# BPU_display.net
KiCad netlist of a schematic drawn in EAGLE
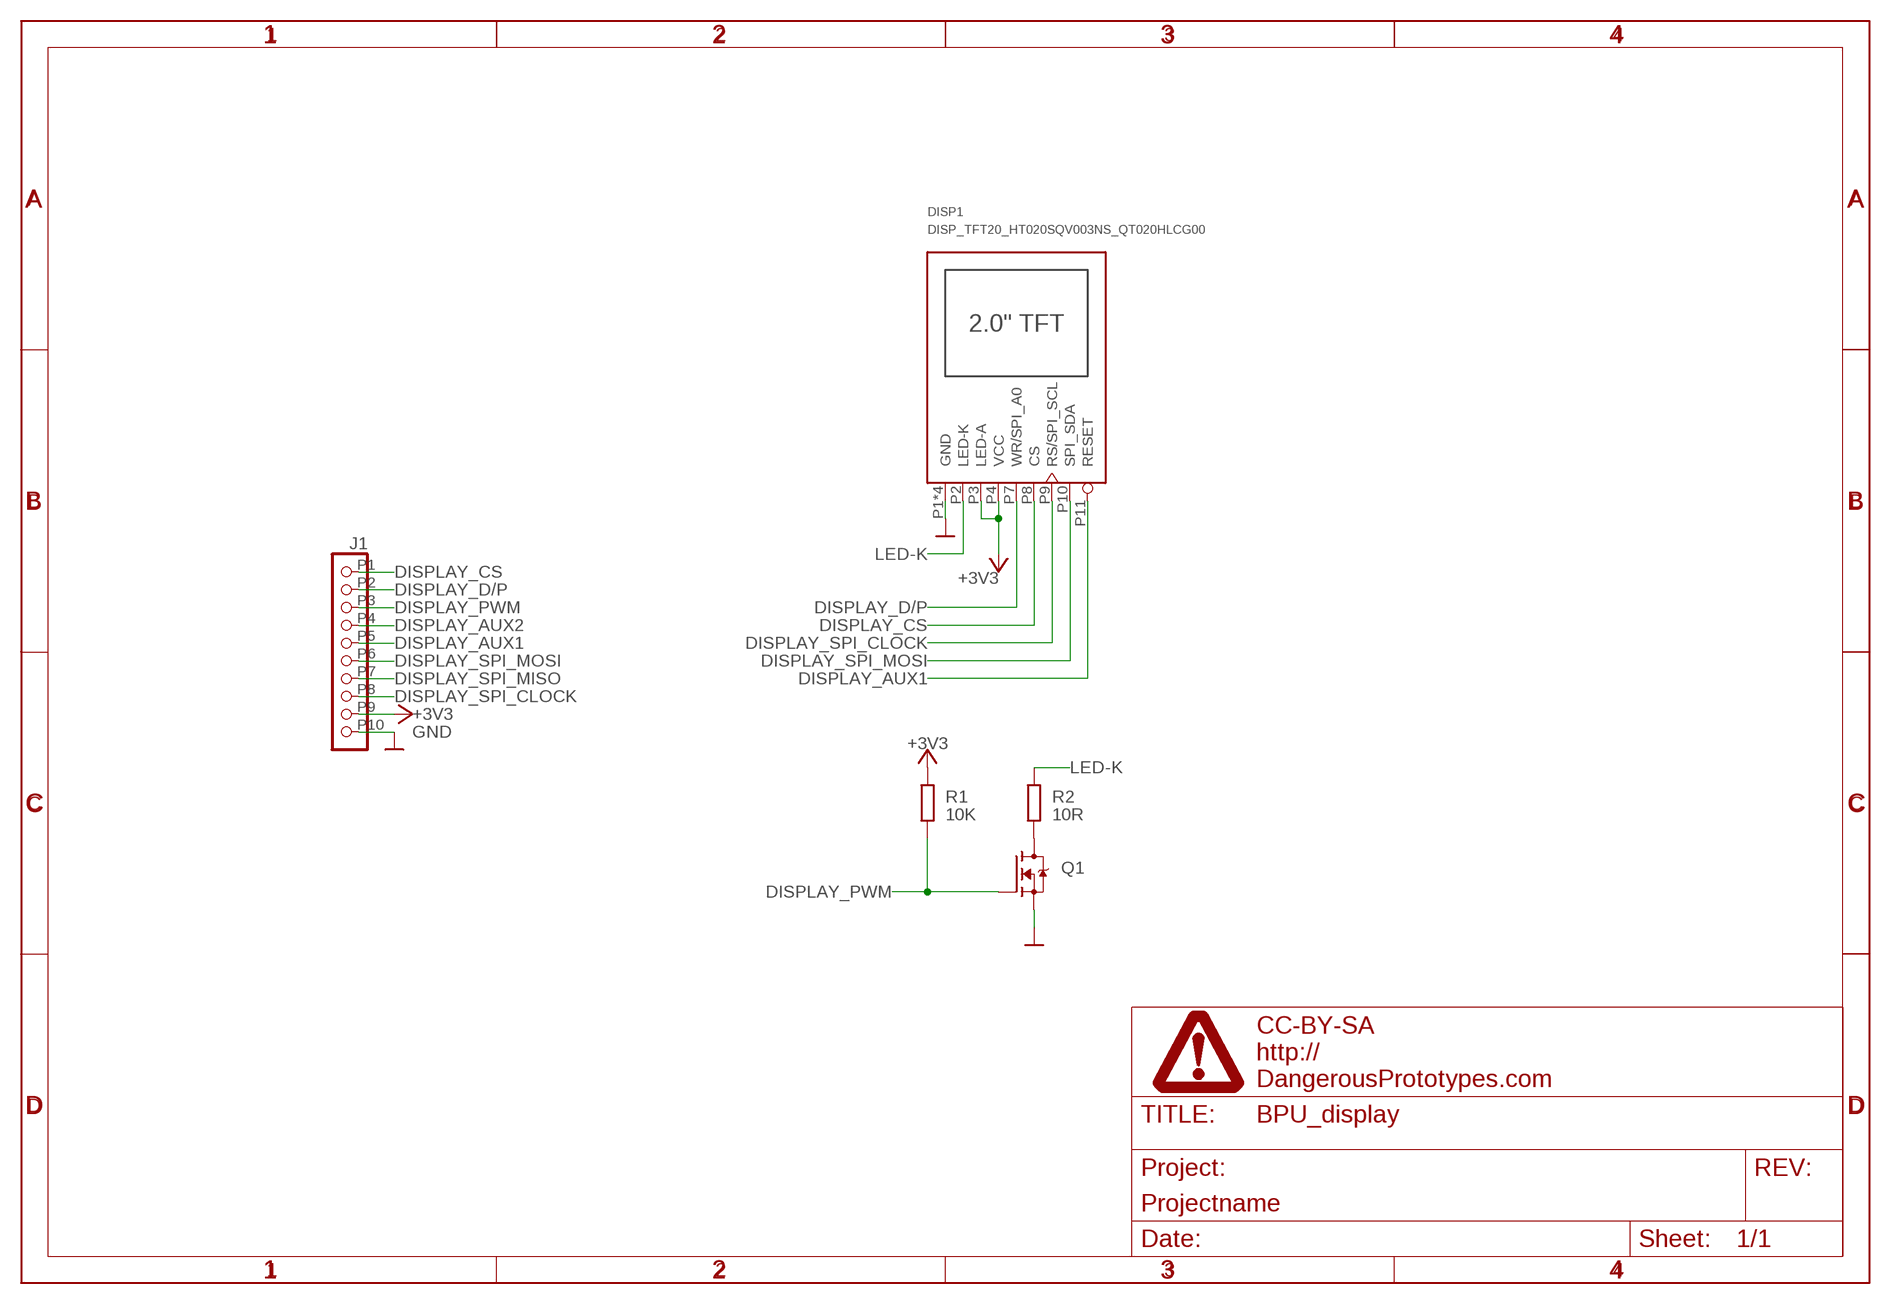
[diagram p0: schematic, sheet 1]

(export (version "E")
  (design (tool "Eeschema 10.0.6"))
  (components
    (comp (ref "DISP1")
      (value "DISP_TFT20_HT020SQV003NS_QT020HLCG00")
      (footprint "eagle-import:HT020SQV003NS_QT020HLCG00")
      (libsource (lib "eagle-import") (part "DISP_TFT20_HT020SQV003NS_QT020HLCG00"))
    )
    (comp (ref "J1")
      (value "CON_MOLEX_MALE_SMT_RIGHT_ANGLE_1.25")
      (footprint "eagle-import:MOLEX_532611071")
      (libsource (lib "eagle-import") (part "CON_MOLEX_MALE_SMT_RIGHT_ANGLE_1.25"))
    )
    (comp (ref "PAGE1")
      (value "FRAME_DINA4_L")
      (footprint "eagle-import:DP_LOGO")
      (libsource (lib "eagle-import") (part "FRAME_DINA4_L"))
    )
    (comp (ref "Q1")
      (value "TRANSISTOR_FET_BS170-SOT-23")
      (footprint "eagle-import:SOT-23")
      (libsource (lib "eagle-import") (part "TRANSISTOR_FET_BS170-SOT-23"))
    )
    (comp (ref "R1")
      (value "10K")
      (footprint "eagle-import:R0603")
      (libsource (lib "eagle-import") (part "R-EU_R0603"))
    )
    (comp (ref "R2")
      (value "10R")
      (footprint "eagle-import:R0603")
      (libsource (lib "eagle-import") (part "R-EU_R0603"))
    )
  )
  (nets
    (net (code "1") (name "/DISPLAY_AUX1") (class "Default")
      (node (ref "DISP1") (pin "P11") (pinfunction "RESET_P11") (pintype "input"))
      (node (ref "J1") (pin "P5") (pinfunction "5_P5") (pintype "passive"))
    )
    (net (code "2") (name "/DISPLAY_AUX2") (class "Default")
      (node (ref "J1") (pin "P4") (pinfunction "4_P4") (pintype "passive"))
    )
    (net (code "3") (name "/DISPLAY_CS") (class "Default")
      (node (ref "DISP1") (pin "P8") (pinfunction "CS_P8") (pintype "input"))
      (node (ref "J1") (pin "P1") (pinfunction "1_P1") (pintype "passive"))
    )
    (net (code "4") (name "/DISPLAY_D{slash}P") (class "Default")
      (node (ref "DISP1") (pin "P7") (pinfunction "WR/SPI_A0_P7") (pintype "input"))
      (node (ref "J1") (pin "P2") (pinfunction "2_P2") (pintype "passive"))
    )
    (net (code "5") (name "/DISPLAY_PWM") (class "Default")
      (node (ref "J1") (pin "P3") (pinfunction "3_P3") (pintype "passive"))
      (node (ref "Q1") (pin "1") (pinfunction "G_1") (pintype "passive"))
      (node (ref "R1") (pin "1") (pinfunction "1_1") (pintype "passive"))
    )
    (net (code "6") (name "/DISPLAY_SPI_CLOCK") (class "Default")
      (node (ref "DISP1") (pin "P9") (pinfunction "RS/SPI_SCL_P9") (pintype "input"))
      (node (ref "J1") (pin "P8") (pinfunction "8_P8") (pintype "passive"))
    )
    (net (code "7") (name "/DISPLAY_SPI_MISO") (class "Default")
      (node (ref "J1") (pin "P7") (pinfunction "7_P7") (pintype "passive"))
    )
    (net (code "8") (name "/DISPLAY_SPI_MOSI") (class "Default")
      (node (ref "DISP1") (pin "P10") (pinfunction "SPI_SDA_P10") (pintype "bidirectional"))
      (node (ref "J1") (pin "P6") (pinfunction "6_P6") (pintype "passive"))
    )
    (net (code "9") (name "/LED-K") (class "Default")
      (node (ref "DISP1") (pin "P2") (pinfunction "LED-K_P2") (pintype "power_in"))
      (node (ref "R2") (pin "2") (pinfunction "2_2") (pintype "passive"))
    )
    (net (code "10") (name "Net-(Q1-D)") (class "Default")
      (node (ref "Q1") (pin "3") (pinfunction "D_3") (pintype "passive"))
      (node (ref "R2") (pin "1") (pinfunction "1_1") (pintype "passive"))
    )
    (net (code "11") (name "SUPPLY_+3V3") (class "Default")
      (node (ref "DISP1") (pin "P3") (pinfunction "LED-A_P3") (pintype "power_in"))
      (node (ref "DISP1") (pin "P4") (pinfunction "VCC_P4") (pintype "power_in"))
      (node (ref "J1") (pin "P9") (pinfunction "9_P9") (pintype "passive"))
      (node (ref "R1") (pin "2") (pinfunction "2_2") (pintype "passive"))
    )
    (net (code "12") (name "SUPPLY_GND") (class "Default")
      (node (ref "DISP1") (pin "P1") (pinfunction "GND_P1") (pintype "power_in"))
      (node (ref "DISP1") (pin "P12") (pinfunction "GND_P12") (pintype "power_in"))
      (node (ref "DISP1") (pin "P5") (pinfunction "GND_P5") (pintype "power_in"))
      (node (ref "DISP1") (pin "P6") (pinfunction "GND_P6") (pintype "power_in"))
      (node (ref "J1") (pin "P10") (pinfunction "10_P10") (pintype "passive"))
      (node (ref "Q1") (pin "2") (pinfunction "S_2") (pintype "passive"))
    )
  )
)
